# TOP_1P.net
KiCad netlist of a schematic drawn in EAGLE
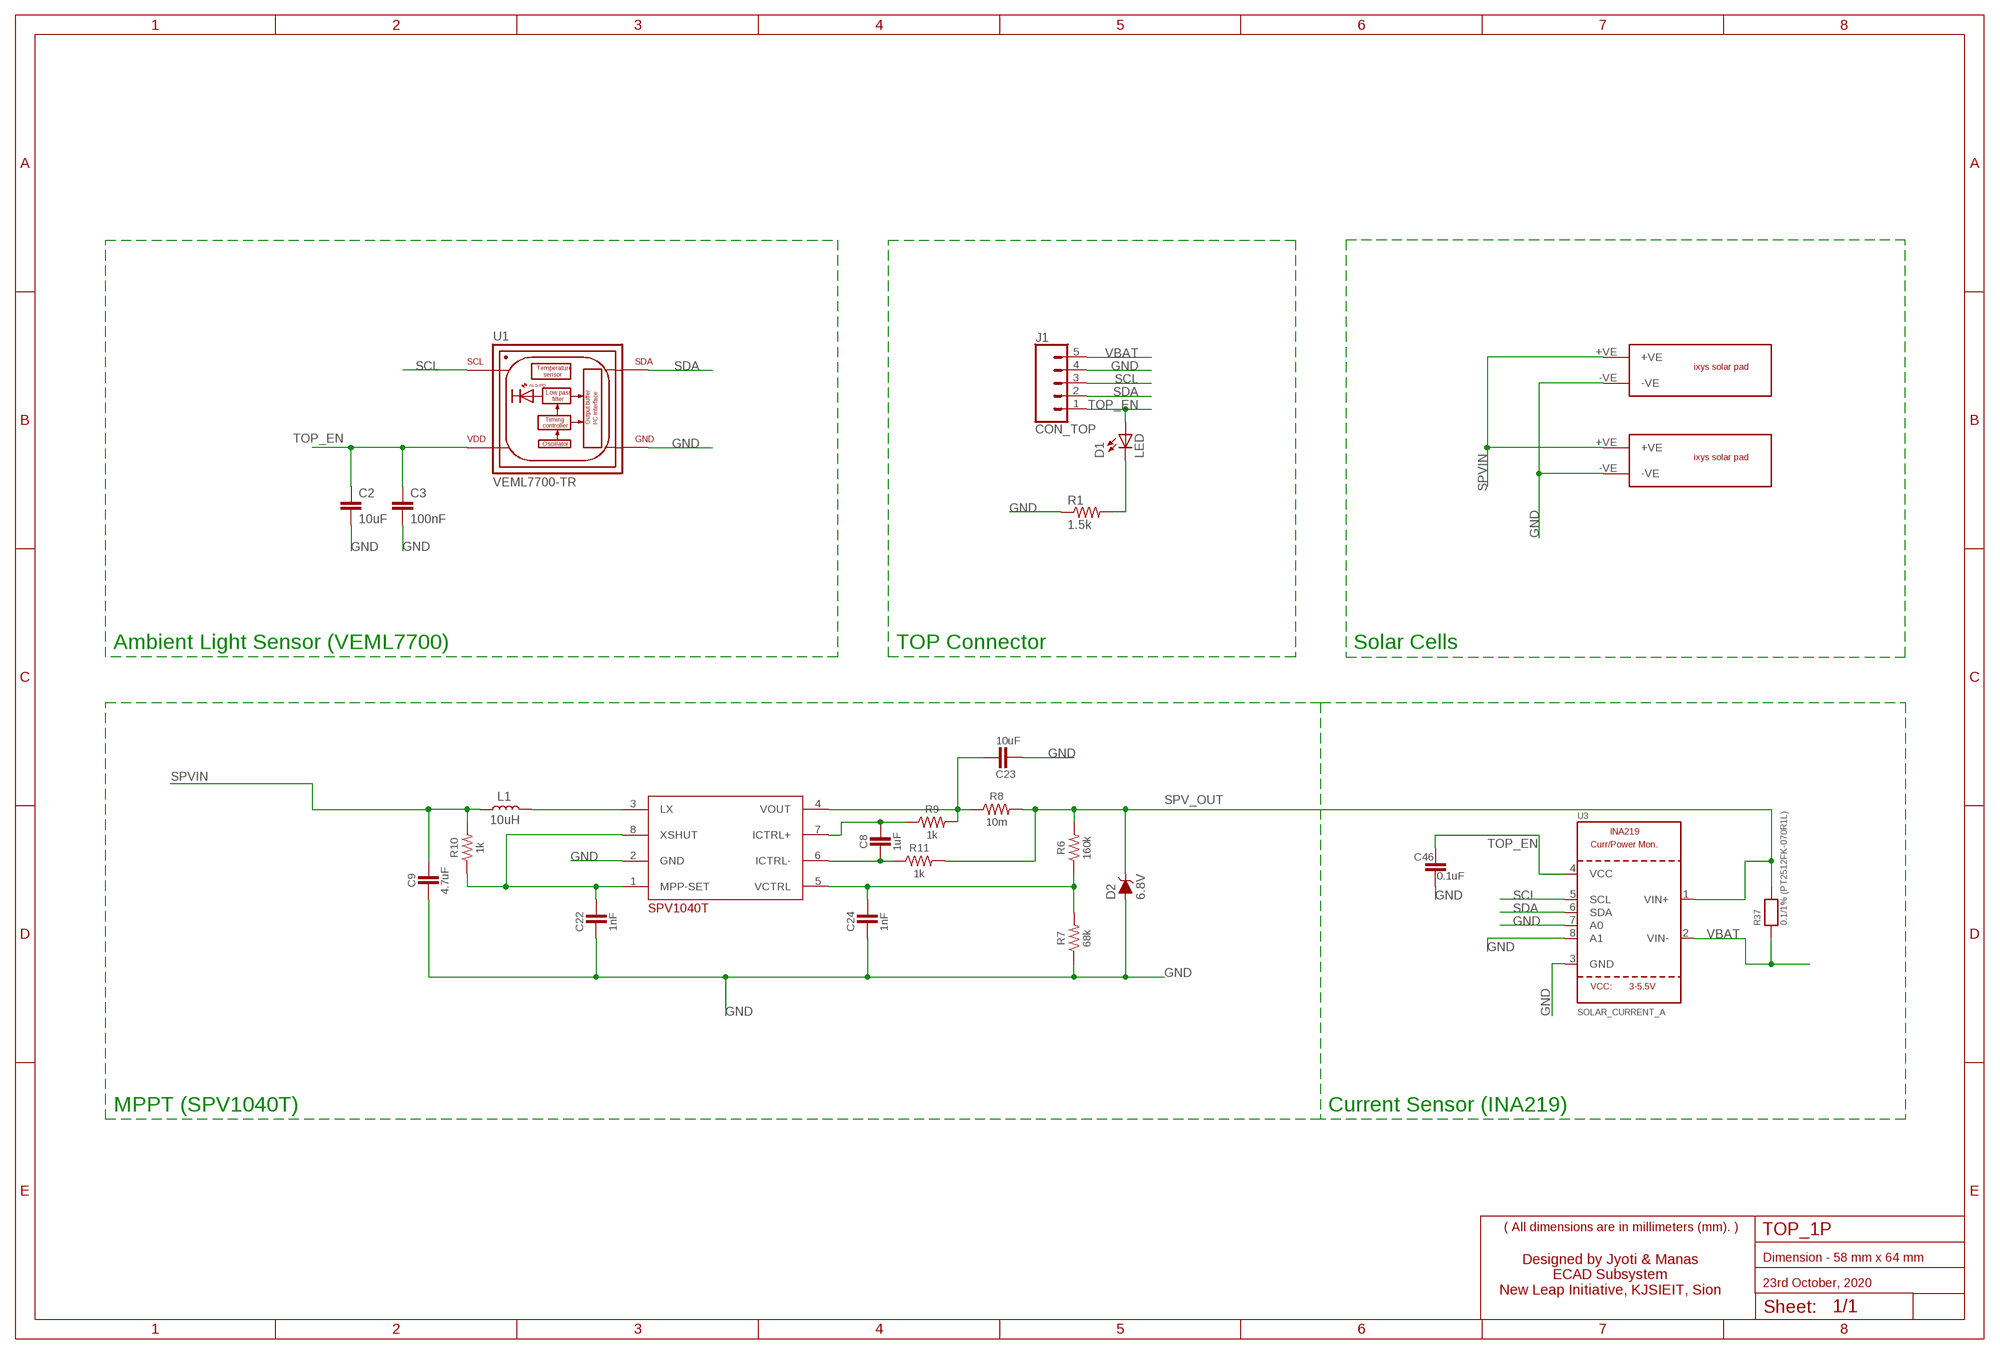
[diagram p0: schematic, sheet 1]

(export (version "E")
  (design (tool "Eeschema 10.0.6"))
  (components
    (comp (ref "C2")
      (value "10uF")
      (footprint "eagle-import:0603")
      (libsource (lib "eagle-import") (part "2.2NF/2200PF-0603-50V-10%"))
    )
    (comp (ref "C3")
      (value "100nF")
      (footprint "eagle-import:0603")
      (libsource (lib "eagle-import") (part "2.2NF/2200PF-0603-50V-10%"))
    )
    (comp (ref "C8")
      (value "1uF")
      (footprint "eagle-import:0603")
      (libsource (lib "eagle-import") (part "10UF-0603-6.3V-20%"))
    )
    (comp (ref "C9")
      (value "4.7uF")
      (footprint "eagle-import:0603")
      (libsource (lib "eagle-import") (part "10UF-0603-6.3V-20%"))
    )
    (comp (ref "C22")
      (value "1nF")
      (footprint "eagle-import:0603")
      (libsource (lib "eagle-import") (part "10UF-0603-6.3V-20%"))
    )
    (comp (ref "C23")
      (value "10uF")
      (footprint "eagle-import:0603")
      (libsource (lib "eagle-import") (part "10UF-0603-6.3V-20%"))
    )
    (comp (ref "C24")
      (value "1nF")
      (footprint "eagle-import:0603")
      (libsource (lib "eagle-import") (part "10UF-0603-6.3V-20%"))
    )
    (comp (ref "C46")
      (value "0.1uF")
      (footprint "eagle-import:0603")
      (libsource (lib "eagle-import") (part "10UF-0603-6.3V-20%"))
    )
    (comp (ref "D2")
      (value "6.8V")
      (footprint "eagle-import:SOD-323")
      (libsource (lib "eagle-import") (part "DIODE-ZENER-MMSZ5232BS"))
    )
    (comp (ref "J1")
      (value "CON_TOP")
      (footprint "eagle-import:1X05_1.27MM")
      (libsource (lib "eagle-import") (part "CONN_051.27MM"))
    )
    (comp (ref "L1")
      (value "10uH")
      (footprint "eagle-import:0603")
      (libsource (lib "eagle-import") (part "INDUCTOR-0603-33NH"))
    )
    (comp (ref "LED")
      (value "D1")
      (footprint "eagle-import:CHIP-LED0603")
      (libsource (lib "eagle-import") (part "LEDCHIP-LED0603"))
    )
    (comp (ref "R1")
      (value "1.5k")
      (footprint "eagle-import:R0603")
      (libsource (lib "eagle-import") (part "R-US_R0603"))
    )
    (comp (ref "R6")
      (value "160k")
      (footprint "eagle-import:RES_0603")
      (fields
        (field (name "DIGIKEY_PART_NUMBER") "311-0.0GRTR-ND")
        (field (name "MANUFACTURER") "Yageo")
        (field (name "MPN") "RC0603JR-070RL")
        (field (name "CREATED_BY") "PCBLayout.com")
      )
      (libsource (lib "eagle-import") (part "RC0603JR-070RL"))
    )
    (comp (ref "R7")
      (value "68k")
      (footprint "eagle-import:RES_0603")
      (fields
        (field (name "DIGIKEY_PART_NUMBER") "311-0.0GRTR-ND")
        (field (name "MANUFACTURER") "Yageo")
        (field (name "MPN") "RC0603JR-070RL")
        (field (name "CREATED_BY") "PCBLayout.com")
      )
      (libsource (lib "eagle-import") (part "RC0603JR-070RL"))
    )
    (comp (ref "R8")
      (value "10m")
      (footprint "eagle-import:RES_0603")
      (fields
        (field (name "DIGIKEY_PART_NUMBER") "311-0.0GRTR-ND")
        (field (name "MANUFACTURER") "Yageo")
        (field (name "MPN") "RC0603JR-070RL")
        (field (name "CREATED_BY") "PCBLayout.com")
      )
      (libsource (lib "eagle-import") (part "RC0603JR-070RL"))
    )
    (comp (ref "R9")
      (value "1k")
      (footprint "eagle-import:RES_0603")
      (fields
        (field (name "DIGIKEY_PART_NUMBER") "311-0.0GRTR-ND")
        (field (name "MANUFACTURER") "Yageo")
        (field (name "MPN") "RC0603JR-070RL")
        (field (name "CREATED_BY") "PCBLayout.com")
      )
      (libsource (lib "eagle-import") (part "RC0603JR-070RL"))
    )
    (comp (ref "R10")
      (value "1k")
      (footprint "eagle-import:RES_0603")
      (fields
        (field (name "DIGIKEY_PART_NUMBER") "311-0.0GRTR-ND")
        (field (name "MANUFACTURER") "Yageo")
        (field (name "MPN") "RC0603JR-070RL")
        (field (name "CREATED_BY") "PCBLayout.com")
      )
      (libsource (lib "eagle-import") (part "RC0603JR-070RL"))
    )
    (comp (ref "R11")
      (value "1k")
      (footprint "eagle-import:RES_0603")
      (fields
        (field (name "DIGIKEY_PART_NUMBER") "311-0.0GRTR-ND")
        (field (name "MANUFACTURER") "Yageo")
        (field (name "MPN") "RC0603JR-070RL")
        (field (name "CREATED_BY") "PCBLayout.com")
      )
      (libsource (lib "eagle-import") (part "RC0603JR-070RL"))
    )
    (comp (ref "R37")
      (value "0.1/1% (PT2512FK-070R1L)")
      (footprint "eagle-import:2512")
      (libsource (lib "eagle-import") (part "RESISTOR2512"))
    )
    (comp (ref "U$1")
      (value "IXYS")
      (footprint "eagle-import:IXYS")
      (libsource (lib "eagle-import") (part "IXYS"))
    )
    (comp (ref "U$2")
      (value "IXYS")
      (footprint "eagle-import:IXYS")
      (libsource (lib "eagle-import") (part "IXYS"))
    )
    (comp (ref "U1")
      (value "VEML7700-TR")
      (footprint "eagle-import:XDCR_VEML7700-TR")
      (fields (field (name "DIGI-KEY_PART_NUMBER") "VEML7700CT-ND") (field (name "MF") "Vishay"))
      (libsource (lib "eagle-import") (part "VEML7700-TR"))
    )
    (comp (ref "U2")
      (value "U2")
      (footprint "eagle-import:SOP65P640X120-8N")
      (libsource (lib "eagle-import") (part "SPV1040T_"))
    )
    (comp (ref "U3")
      (value "SOLAR_CURRENT_A")
      (footprint "eagle-import:SOT23-8")
      (libsource (lib "eagle-import") (part "INA219"))
    )
  )
  (nets
    (net (code "1") (name "/GND") (class "Default")
      (node (ref "C2") (pin "2") (pinfunction "2_2") (pintype "passive"))
      (node (ref "C22") (pin "2") (pinfunction "2_2") (pintype "passive"))
      (node (ref "C23") (pin "2") (pinfunction "2_2") (pintype "passive"))
      (node (ref "C24") (pin "2") (pinfunction "2_2") (pintype "passive"))
      (node (ref "C3") (pin "2") (pinfunction "2_2") (pintype "passive"))
      (node (ref "C46") (pin "2") (pinfunction "2_2") (pintype "passive"))
      (node (ref "C9") (pin "2") (pinfunction "2_2") (pintype "passive"))
      (node (ref "D2") (pin "A") (pinfunction "A_A") (pintype "passive"))
      (node (ref "J1") (pin "4") (pinfunction "4_4") (pintype "passive"))
      (node (ref "R1") (pin "1") (pinfunction "1_1") (pintype "passive"))
      (node (ref "R7") (pin "1") (pinfunction "1_1") (pintype "passive"))
      (node (ref "U$1") (pin "-VE") (pinfunction "-VE_-VE") (pintype "bidirectional"))
      (node (ref "U$2") (pin "-VE") (pinfunction "-VE_-VE") (pintype "bidirectional"))
      (node (ref "U1") (pin "3") (pinfunction "GND_3") (pintype "power_in"))
      (node (ref "U2") (pin "2") (pinfunction "GND_2") (pintype "bidirectional"))
      (node (ref "U3") (pin "3") (pinfunction "GND_3") (pintype "bidirectional"))
      (node (ref "U3") (pin "7") (pinfunction "A0_7") (pintype "bidirectional"))
      (node (ref "U3") (pin "8") (pinfunction "A1_8") (pintype "bidirectional"))
    )
    (net (code "2") (name "/SCL") (class "Default")
      (node (ref "J1") (pin "3") (pinfunction "3_3") (pintype "passive"))
      (node (ref "U1") (pin "1") (pinfunction "SCL_1") (pintype "input"))
      (node (ref "U3") (pin "5") (pinfunction "SCL_5") (pintype "bidirectional"))
    )
    (net (code "3") (name "/SDA") (class "Default")
      (node (ref "J1") (pin "2") (pinfunction "2_2") (pintype "passive"))
      (node (ref "U1") (pin "4") (pinfunction "SDA_4") (pintype "bidirectional"))
      (node (ref "U3") (pin "6") (pinfunction "SDA_6") (pintype "bidirectional"))
    )
    (net (code "4") (name "/SPVIN") (class "Default")
      (node (ref "C9") (pin "1") (pinfunction "1_1") (pintype "passive"))
      (node (ref "L1") (pin "1") (pinfunction "1_1") (pintype "passive"))
      (node (ref "R10") (pin "2") (pinfunction "2_2") (pintype "passive"))
      (node (ref "U$1") (pin "+VE") (pinfunction "+VE_+VE") (pintype "bidirectional"))
      (node (ref "U$2") (pin "+VE") (pinfunction "+VE_+VE") (pintype "bidirectional"))
    )
    (net (code "5") (name "/SPV_OUT") (class "Default")
      (node (ref "D2") (pin "C") (pinfunction "C_C") (pintype "passive"))
      (node (ref "R11") (pin "2") (pinfunction "2_2") (pintype "passive"))
      (node (ref "R37") (pin "2") (pinfunction "2_2") (pintype "passive"))
      (node (ref "R6") (pin "2") (pinfunction "2_2") (pintype "passive"))
      (node (ref "R8") (pin "2") (pinfunction "2_2") (pintype "passive"))
      (node (ref "U3") (pin "1") (pinfunction "VIN+_1") (pintype "bidirectional"))
    )
    (net (code "6") (name "/TOP_EN") (class "Default")
      (node (ref "C2") (pin "1") (pinfunction "1_1") (pintype "passive"))
      (node (ref "C3") (pin "1") (pinfunction "1_1") (pintype "passive"))
      (node (ref "C46") (pin "1") (pinfunction "1_1") (pintype "passive"))
      (node (ref "J1") (pin "1") (pinfunction "1_1") (pintype "passive"))
      (node (ref "LED") (pin "A") (pinfunction "A_A") (pintype "passive"))
      (node (ref "U1") (pin "2") (pinfunction "VDD_2") (pintype "power_in"))
      (node (ref "U3") (pin "4") (pinfunction "VCC_4") (pintype "bidirectional"))
    )
    (net (code "7") (name "/VBAT") (class "Default")
      (node (ref "J1") (pin "5") (pinfunction "5_5") (pintype "passive"))
      (node (ref "R37") (pin "1") (pinfunction "1_1") (pintype "passive"))
      (node (ref "U3") (pin "2") (pinfunction "VIN-_2") (pintype "bidirectional"))
    )
    (net (code "8") (name "Net-(LED-PadC)") (class "Default")
      (node (ref "LED") (pin "C") (pinfunction "C_C") (pintype "passive"))
      (node (ref "R1") (pin "2") (pinfunction "2_2") (pintype "passive"))
    )
    (net (code "9") (name "Net-(U2-ICTRL+)") (class "Default")
      (node (ref "C8") (pin "1") (pinfunction "1_1") (pintype "passive"))
      (node (ref "R9") (pin "1") (pinfunction "1_1") (pintype "passive"))
      (node (ref "U2") (pin "7") (pinfunction "ICTRL+_7") (pintype "bidirectional"))
    )
    (net (code "10") (name "Net-(U2-ICTRL-)") (class "Default")
      (node (ref "C8") (pin "2") (pinfunction "2_2") (pintype "passive"))
      (node (ref "R11") (pin "1") (pinfunction "1_1") (pintype "passive"))
      (node (ref "U2") (pin "6") (pinfunction "ICTRL-_6") (pintype "bidirectional"))
    )
    (net (code "11") (name "Net-(U2-LX)") (class "Default")
      (node (ref "L1") (pin "2") (pinfunction "2_2") (pintype "passive"))
      (node (ref "U2") (pin "3") (pinfunction "LX_3") (pintype "bidirectional"))
    )
    (net (code "12") (name "Net-(U2-MPP-SET)") (class "Default")
      (node (ref "C22") (pin "1") (pinfunction "1_1") (pintype "passive"))
      (node (ref "R10") (pin "1") (pinfunction "1_1") (pintype "passive"))
      (node (ref "U2") (pin "1") (pinfunction "MPP-SET_1") (pintype "bidirectional"))
      (node (ref "U2") (pin "8") (pinfunction "XSHUT_8") (pintype "bidirectional"))
    )
    (net (code "13") (name "Net-(U2-VCTRL)") (class "Default")
      (node (ref "C24") (pin "1") (pinfunction "1_1") (pintype "passive"))
      (node (ref "R6") (pin "1") (pinfunction "1_1") (pintype "passive"))
      (node (ref "R7") (pin "2") (pinfunction "2_2") (pintype "passive"))
      (node (ref "U2") (pin "5") (pinfunction "VCTRL_5") (pintype "bidirectional"))
    )
    (net (code "14") (name "Net-(U2-VOUT)") (class "Default")
      (node (ref "C23") (pin "1") (pinfunction "1_1") (pintype "passive"))
      (node (ref "R8") (pin "1") (pinfunction "1_1") (pintype "passive"))
      (node (ref "R9") (pin "2") (pinfunction "2_2") (pintype "passive"))
      (node (ref "U2") (pin "4") (pinfunction "VOUT_4") (pintype "bidirectional"))
    )
  )
)
